# Magic_Key.net
KiCad netlist of a schematic drawn in EAGLE
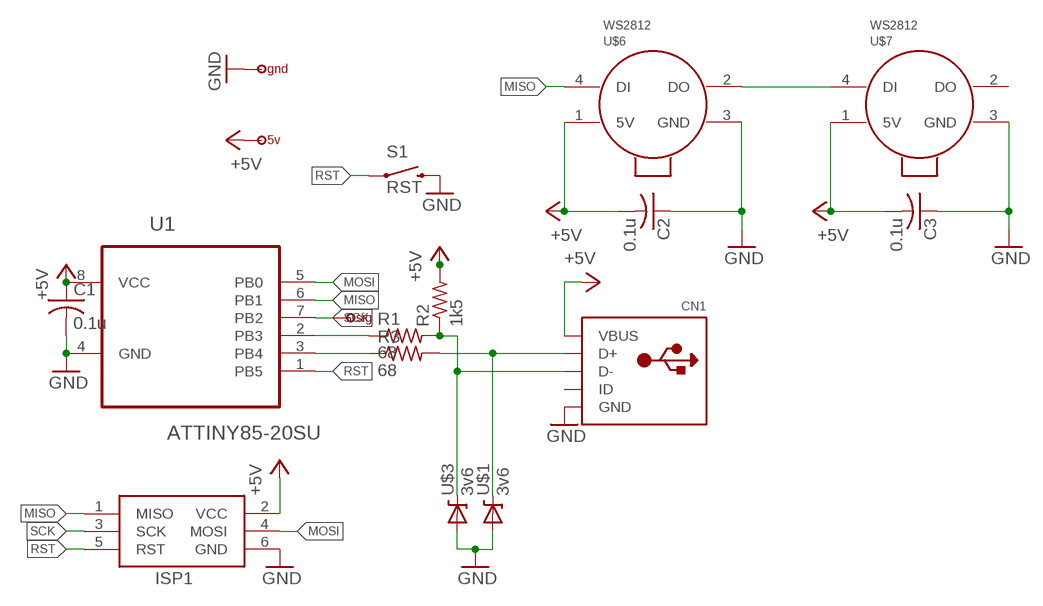
[diagram p0: schematic, sheet 1]

(export (version "E")
  (design (tool "Eeschema 10.0.6"))
  (components
    (comp (ref "C1")
      (value "0.1u")
      (footprint "eagle-import:C0603")
      (libsource (lib "eagle-import") (part "C-USC0603"))
    )
    (comp (ref "C2")
      (value "0.1u")
      (footprint "eagle-import:C0603")
      (libsource (lib "eagle-import") (part "C-USC0603"))
    )
    (comp (ref "C3")
      (value "0.1u")
      (footprint "eagle-import:C0603")
      (libsource (lib "eagle-import") (part "C-USC0603"))
    )
    (comp (ref "CN1")
      (value "USB_LEGS")
      (footprint "eagle-import:MICRO_USB_LEGS")
      (libsource (lib "eagle-import") (part "USB_LEGS"))
    )
    (comp (ref "ISP1")
      (value "AVRISP-6")
      (footprint "eagle-import:AVRISP")
      (libsource (lib "eagle-import") (part "AVRISP-6"))
    )
    (comp (ref "R1")
      (value "68")
      (footprint "eagle-import:R0603")
      (libsource (lib "eagle-import") (part "R-US_R0603"))
    )
    (comp (ref "R2")
      (value "1k5")
      (footprint "eagle-import:R0603")
      (libsource (lib "eagle-import") (part "R-US_R0603"))
    )
    (comp (ref "R3")
      (value "68")
      (footprint "eagle-import:R0603")
      (libsource (lib "eagle-import") (part "R-US_R0603"))
    )
    (comp (ref "S1")
      (value "RST")
      (footprint "eagle-import:TACTILE-SWITCH-SMD")
      (libsource (lib "eagle-import") (part "SWITCH-MOMENTARY-2SMD"))
    )
    (comp (ref "U$1")
      (value "3v6")
      (footprint "eagle-import:SOD-323")
      (libsource (lib "eagle-import") (part "DIODE-ZENER-BZT52"))
    )
    (comp (ref "U$2")
      (value "gnd")
      (footprint "eagle-import:1PIN")
      (libsource (lib "eagle-import") (part "1PINBIG"))
    )
    (comp (ref "U$3")
      (value "3v6")
      (footprint "eagle-import:SOD-323")
      (libsource (lib "eagle-import") (part "DIODE-ZENER-BZT52"))
    )
    (comp (ref "U$4")
      (value "sig")
      (footprint "eagle-import:1PIN")
      (libsource (lib "eagle-import") (part "1PINBIG"))
    )
    (comp (ref "U$5")
      (value "5v")
      (footprint "eagle-import:1PIN")
      (libsource (lib "eagle-import") (part "1PINBIG"))
    )
    (comp (ref "U$6")
      (value "WS2812")
      (footprint "eagle-import:WS2812")
      (libsource (lib "eagle-import") (part "WS2812"))
    )
    (comp (ref "U$7")
      (value "WS2812")
      (footprint "eagle-import:WS2812")
      (libsource (lib "eagle-import") (part "WS2812"))
    )
    (comp (ref "U1")
      (value "ATTINY85-20SU")
      (footprint "eagle-import:SOIC127P798X216-8N")
      (libsource (lib "eagle-import") (part "ATTINY85-20SU"))
    )
  )
  (nets
    (net (code "1") (name "+5V") (class "Default")
      (node (ref "C1") (pin "1") (pinfunction "1_1") (pintype "passive"))
      (node (ref "C2") (pin "2") (pinfunction "2_2") (pintype "passive"))
      (node (ref "C3") (pin "2") (pinfunction "2_2") (pintype "passive"))
      (node (ref "CN1") (pin "5") (pinfunction "VBUS_5") (pintype "power_in"))
      (node (ref "ISP1") (pin "2") (pinfunction "VCC_2") (pintype "power_in"))
      (node (ref "R2") (pin "2") (pinfunction "2_2") (pintype "passive"))
      (node (ref "U$5") (pin "P$1") (pinfunction ">NAME_P$1") (pintype "bidirectional"))
      (node (ref "U$6") (pin "1") (pinfunction "5V_1") (pintype "bidirectional"))
      (node (ref "U$7") (pin "1") (pinfunction "5V_1") (pintype "bidirectional"))
      (node (ref "U1") (pin "8") (pinfunction "VCC_8") (pintype "power_in"))
    )
    (net (code "2") (name "GND") (class "Default")
      (node (ref "C1") (pin "2") (pinfunction "2_2") (pintype "passive"))
      (node (ref "C2") (pin "1") (pinfunction "1_1") (pintype "passive"))
      (node (ref "C3") (pin "1") (pinfunction "1_1") (pintype "passive"))
      (node (ref "CN1") (pin "1") (pinfunction "GND_1") (pintype "power_in"))
      (node (ref "ISP1") (pin "6") (pinfunction "GND_6") (pintype "power_in"))
      (node (ref "S1") (pin "3") (pinfunction "2_3") (pintype "passive"))
      (node (ref "U$1") (pin "2") (pinfunction "A_2") (pintype "passive"))
      (node (ref "U$2") (pin "P$1") (pinfunction ">NAME_P$1") (pintype "bidirectional"))
      (node (ref "U$3") (pin "2") (pinfunction "A_2") (pintype "passive"))
      (node (ref "U$6") (pin "3") (pinfunction "GND_3") (pintype "bidirectional"))
      (node (ref "U$7") (pin "3") (pinfunction "GND_3") (pintype "bidirectional"))
      (node (ref "U1") (pin "4") (pinfunction "GND_4") (pintype "passive"))
    )
    (net (code "3") (name "MISO") (class "Default")
      (node (ref "ISP1") (pin "1") (pinfunction "MISO_1") (pintype "input"))
      (node (ref "U$6") (pin "4") (pinfunction "DI_4") (pintype "bidirectional"))
      (node (ref "U1") (pin "6") (pinfunction "PB1_6") (pintype "bidirectional"))
    )
    (net (code "4") (name "MOSI") (class "Default")
      (node (ref "ISP1") (pin "4") (pinfunction "MOSI_4") (pintype "output"))
      (node (ref "U1") (pin "5") (pinfunction "PB0_5") (pintype "bidirectional"))
    )
    (net (code "5") (name "Net-(CN1-D+)") (class "Default")
      (node (ref "CN1") (pin "3") (pinfunction "D+_3") (pintype "bidirectional"))
      (node (ref "R3") (pin "2") (pinfunction "2_2") (pintype "passive"))
      (node (ref "U$1") (pin "1") (pinfunction "C_1") (pintype "passive"))
    )
    (net (code "6") (name "Net-(CN1-D-)") (class "Default")
      (node (ref "CN1") (pin "4") (pinfunction "D-_4") (pintype "bidirectional"))
      (node (ref "R1") (pin "2") (pinfunction "2_2") (pintype "passive"))
      (node (ref "R2") (pin "1") (pinfunction "1_1") (pintype "passive"))
      (node (ref "U$3") (pin "1") (pinfunction "C_1") (pintype "passive"))
    )
    (net (code "7") (name "Net-(U$6-DO)") (class "Default")
      (node (ref "U$6") (pin "2") (pinfunction "DO_2") (pintype "bidirectional"))
      (node (ref "U$7") (pin "4") (pinfunction "DI_4") (pintype "bidirectional"))
    )
    (net (code "8") (name "Net-(U1-PB3)") (class "Default")
      (node (ref "R1") (pin "1") (pinfunction "1_1") (pintype "passive"))
      (node (ref "U1") (pin "2") (pinfunction "PB3_2") (pintype "bidirectional"))
    )
    (net (code "9") (name "Net-(U1-PB4)") (class "Default")
      (node (ref "R3") (pin "1") (pinfunction "1_1") (pintype "passive"))
      (node (ref "U1") (pin "3") (pinfunction "PB4_3") (pintype "bidirectional"))
    )
    (net (code "10") (name "RST") (class "Default")
      (node (ref "ISP1") (pin "5") (pinfunction "RST_5") (pintype "output"))
      (node (ref "S1") (pin "1") (pinfunction "1_1") (pintype "passive"))
      (node (ref "U1") (pin "1") (pinfunction "PB5_1") (pintype "bidirectional"))
    )
    (net (code "11") (name "SCK") (class "Default")
      (node (ref "ISP1") (pin "3") (pinfunction "SCK_3") (pintype "output"))
      (node (ref "U$4") (pin "P$1") (pinfunction ">NAME_P$1") (pintype "bidirectional"))
      (node (ref "U1") (pin "7") (pinfunction "PB2_7") (pintype "bidirectional"))
    )
    (net (code "12") (name "unconnected-(CN1-ID-Pad2)") (class "Default")
      (node (ref "CN1") (pin "2") (pinfunction "ID_2") (pintype "bidirectional"))
    )
    (net (code "13") (name "unconnected-(U$7-DO-Pad2)") (class "Default")
      (node (ref "U$7") (pin "2") (pinfunction "DO_2") (pintype "bidirectional"))
    )
  )
)
